# PortableECG.net
KiCad netlist of a schematic drawn in EAGLE
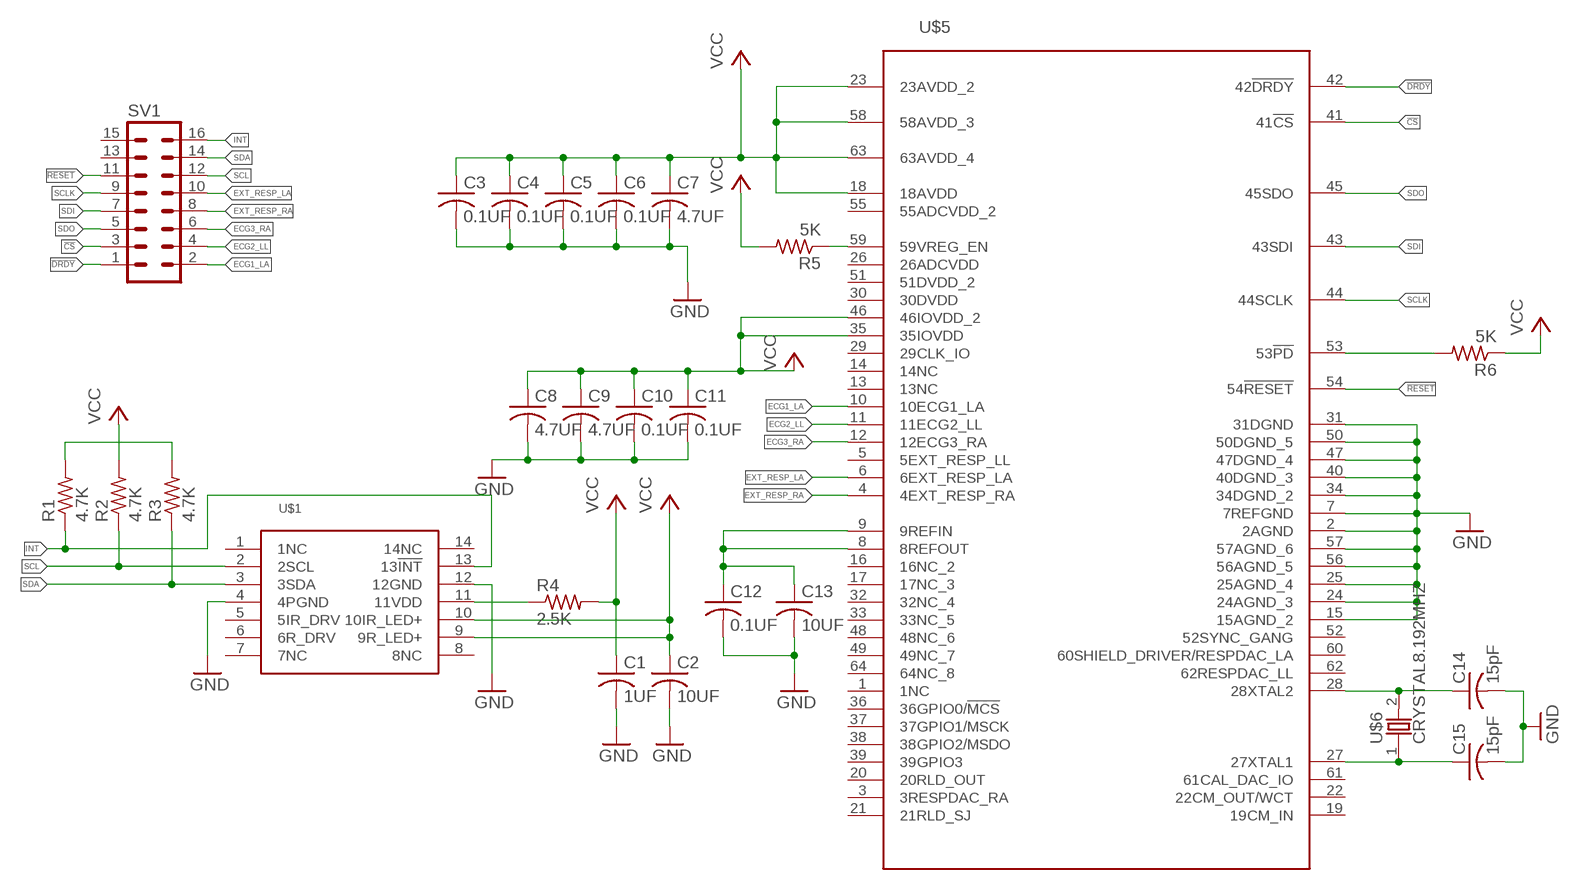
[diagram p0: schematic, sheet 1]

(export (version "E")
  (design (tool "Eeschema 10.0.6"))
  (components
    (comp (ref "C1")
      (value "1UF")
      (footprint "eagle-import:C075-063X106")
      (libsource (lib "eagle-import") (part "C-US075-063X106"))
    )
    (comp (ref "C2")
      (value "10UF")
      (footprint "eagle-import:C075-063X106")
      (libsource (lib "eagle-import") (part "C-US075-063X106"))
    )
    (comp (ref "C3")
      (value "0.1UF")
      (footprint "eagle-import:C075-063X106")
      (libsource (lib "eagle-import") (part "C-US075-063X106"))
    )
    (comp (ref "C4")
      (value "0.1UF")
      (footprint "eagle-import:C075-063X106")
      (libsource (lib "eagle-import") (part "C-US075-063X106"))
    )
    (comp (ref "C5")
      (value "0.1UF")
      (footprint "eagle-import:C075-063X106")
      (libsource (lib "eagle-import") (part "C-US075-063X106"))
    )
    (comp (ref "C6")
      (value "0.1UF")
      (footprint "eagle-import:C075-063X106")
      (libsource (lib "eagle-import") (part "C-US075-063X106"))
    )
    (comp (ref "C7")
      (value "4.7UF")
      (footprint "eagle-import:C075-063X106")
      (libsource (lib "eagle-import") (part "C-US075-063X106"))
    )
    (comp (ref "C8")
      (value "4.7UF")
      (footprint "eagle-import:C075-063X106")
      (libsource (lib "eagle-import") (part "C-US075-063X106"))
    )
    (comp (ref "C9")
      (value "4.7UF")
      (footprint "eagle-import:C075-063X106")
      (libsource (lib "eagle-import") (part "C-US075-063X106"))
    )
    (comp (ref "C10")
      (value "0.1UF")
      (footprint "eagle-import:C075-063X106")
      (libsource (lib "eagle-import") (part "C-US075-063X106"))
    )
    (comp (ref "C11")
      (value "0.1UF")
      (footprint "eagle-import:C075-063X106")
      (libsource (lib "eagle-import") (part "C-US075-063X106"))
    )
    (comp (ref "C12")
      (value "0.1UF")
      (footprint "eagle-import:C075-063X106")
      (libsource (lib "eagle-import") (part "C-US075-063X106"))
    )
    (comp (ref "C13")
      (value "10UF")
      (footprint "eagle-import:C075-063X106")
      (libsource (lib "eagle-import") (part "C-US075-063X106"))
    )
    (comp (ref "C14")
      (value "15pF")
      (footprint "eagle-import:C075-063X106")
      (libsource (lib "eagle-import") (part "C-US075-063X106"))
    )
    (comp (ref "C15")
      (value "15pF")
      (footprint "eagle-import:C075-063X106")
      (libsource (lib "eagle-import") (part "C-US075-063X106"))
    )
    (comp (ref "R1")
      (value "4.7K")
      (footprint "eagle-import:0207_12")
      (libsource (lib "eagle-import") (part "R-US_0207/12"))
    )
    (comp (ref "R2")
      (value "4.7K")
      (footprint "eagle-import:0207_12")
      (libsource (lib "eagle-import") (part "R-US_0207/12"))
    )
    (comp (ref "R3")
      (value "4.7K")
      (footprint "eagle-import:0207_12")
      (libsource (lib "eagle-import") (part "R-US_0207/12"))
    )
    (comp (ref "R4")
      (value "2.5K")
      (footprint "eagle-import:0207_12")
      (libsource (lib "eagle-import") (part "R-US_0207/12"))
    )
    (comp (ref "R5")
      (value "5K")
      (footprint "eagle-import:0207_12")
      (libsource (lib "eagle-import") (part "R-US_0207/12"))
    )
    (comp (ref "R6")
      (value "5K")
      (footprint "eagle-import:0207_12")
      (libsource (lib "eagle-import") (part "R-US_0207/12"))
    )
    (comp (ref "SV1")
      (value "16P")
      (footprint "eagle-import:16P")
      (libsource (lib "eagle-import") (part "16P"))
    )
    (comp (ref "U$1")
      (value "MAX30100DP")
      (footprint "eagle-import:MAX30100DP")
      (libsource (lib "eagle-import") (part "MAX30100DP"))
    )
    (comp (ref "U$5")
      (value "ADAS1000-4BSTZDP")
      (footprint "eagle-import:ADAS1000-4BSTZDP")
      (libsource (lib "eagle-import") (part "ADAS1000-4BSTZDP"))
    )
    (comp (ref "U$6")
      (value "CRYSTAL8.192MHZ")
      (footprint "eagle-import:CRYSTAL8.192MHZ")
      (libsource (lib "eagle-import") (part "CRYSTAL8.192MHZ"))
    )
  )
  (nets
    (net (code "1") (name "/~{CS}") (class "Default")
      (node (ref "SV1") (pin "3") (pinfunction "3_3") (pintype "passive"))
      (node (ref "U$5") (pin "41") (pinfunction "41~{CS}_41") (pintype "bidirectional"))
    )
    (net (code "2") (name "/~{DRDY}") (class "Default")
      (node (ref "SV1") (pin "1") (pinfunction "1_1") (pintype "passive"))
      (node (ref "U$5") (pin "42") (pinfunction "42~{DRDY}_42") (pintype "output"))
    )
    (net (code "3") (name "/~{RESET}") (class "Default")
      (node (ref "SV1") (pin "11") (pinfunction "11_11") (pintype "passive"))
      (node (ref "U$5") (pin "54") (pinfunction "54~{RESET}_54") (pintype "bidirectional"))
    )
    (net (code "4") (name "ECG1_LA") (class "Default")
      (node (ref "SV1") (pin "2") (pinfunction "2_2") (pintype "passive"))
      (node (ref "U$5") (pin "10") (pinfunction "10ECG1_LA_10") (pintype "bidirectional"))
    )
    (net (code "5") (name "ECG2_LL") (class "Default")
      (node (ref "SV1") (pin "4") (pinfunction "4_4") (pintype "passive"))
      (node (ref "U$5") (pin "11") (pinfunction "11ECG2_LL_11") (pintype "bidirectional"))
    )
    (net (code "6") (name "ECG3_RA") (class "Default")
      (node (ref "SV1") (pin "6") (pinfunction "6_6") (pintype "passive"))
      (node (ref "U$5") (pin "12") (pinfunction "12ECG3_RA_12") (pintype "bidirectional"))
    )
    (net (code "7") (name "EXT_RESP_LA") (class "Default")
      (node (ref "SV1") (pin "10") (pinfunction "10_10") (pintype "passive"))
      (node (ref "U$5") (pin "6") (pinfunction "6EXT_RESP_LA_6") (pintype "bidirectional"))
    )
    (net (code "8") (name "EXT_RESP_RA") (class "Default")
      (node (ref "SV1") (pin "8") (pinfunction "8_8") (pintype "passive"))
      (node (ref "U$5") (pin "4") (pinfunction "4EXT_RESP_RA_4") (pintype "bidirectional"))
    )
    (net (code "9") (name "GND") (class "Default")
      (node (ref "C1") (pin "2") (pinfunction "2_2") (pintype "passive"))
      (node (ref "C10") (pin "2") (pinfunction "2_2") (pintype "passive"))
      (node (ref "C11") (pin "2") (pinfunction "2_2") (pintype "passive"))
      (node (ref "C12") (pin "2") (pinfunction "2_2") (pintype "passive"))
      (node (ref "C13") (pin "2") (pinfunction "2_2") (pintype "passive"))
      (node (ref "C14") (pin "2") (pinfunction "2_2") (pintype "passive"))
      (node (ref "C15") (pin "2") (pinfunction "2_2") (pintype "passive"))
      (node (ref "C2") (pin "2") (pinfunction "2_2") (pintype "passive"))
      (node (ref "C3") (pin "2") (pinfunction "2_2") (pintype "passive"))
      (node (ref "C4") (pin "2") (pinfunction "2_2") (pintype "passive"))
      (node (ref "C5") (pin "2") (pinfunction "2_2") (pintype "passive"))
      (node (ref "C6") (pin "2") (pinfunction "2_2") (pintype "passive"))
      (node (ref "C7") (pin "2") (pinfunction "2_2") (pintype "passive"))
      (node (ref "C8") (pin "2") (pinfunction "2_2") (pintype "passive"))
      (node (ref "C9") (pin "2") (pinfunction "2_2") (pintype "passive"))
      (node (ref "U$1") (pin "12") (pinfunction "12GND_12") (pintype "bidirectional"))
      (node (ref "U$1") (pin "4") (pinfunction "4PGND_4") (pintype "bidirectional"))
      (node (ref "U$5") (pin "15") (pinfunction "15AGND_2_15") (pintype "bidirectional"))
      (node (ref "U$5") (pin "2") (pinfunction "2AGND_2") (pintype "bidirectional"))
      (node (ref "U$5") (pin "24") (pinfunction "24AGND_3_24") (pintype "bidirectional"))
      (node (ref "U$5") (pin "25") (pinfunction "25AGND_4_25") (pintype "bidirectional"))
      (node (ref "U$5") (pin "31") (pinfunction "31DGND_31") (pintype "bidirectional"))
      (node (ref "U$5") (pin "34") (pinfunction "34DGND_2_34") (pintype "bidirectional"))
      (node (ref "U$5") (pin "40") (pinfunction "40DGND_3_40") (pintype "bidirectional"))
      (node (ref "U$5") (pin "47") (pinfunction "47DGND_4_47") (pintype "bidirectional"))
      (node (ref "U$5") (pin "50") (pinfunction "50DGND_5_50") (pintype "bidirectional"))
      (node (ref "U$5") (pin "56") (pinfunction "56AGND_5_56") (pintype "bidirectional"))
      (node (ref "U$5") (pin "57") (pinfunction "57AGND_6_57") (pintype "bidirectional"))
      (node (ref "U$5") (pin "7") (pinfunction "7REFGND_7") (pintype "bidirectional"))
    )
    (net (code "10") (name "INT") (class "Default")
      (node (ref "R1") (pin "1") (pinfunction "1_1") (pintype "passive"))
      (node (ref "SV1") (pin "16") (pinfunction "16_16") (pintype "passive"))
      (node (ref "U$1") (pin "13") (pinfunction "13~{INT}_13") (pintype "bidirectional"))
    )
    (net (code "11") (name "Net-(R1-Pad2)") (class "Default")
      (node (ref "R1") (pin "2") (pinfunction "2_2") (pintype "passive"))
      (node (ref "R3") (pin "2") (pinfunction "2_2") (pintype "passive"))
    )
    (net (code "12") (name "Net-(U$1-11VDD)") (class "Default")
      (node (ref "R4") (pin "1") (pinfunction "1_1") (pintype "passive"))
      (node (ref "U$1") (pin "11") (pinfunction "11VDD_11") (pintype "bidirectional"))
    )
    (net (code "13") (name "Net-(U$5-8REFOUT)") (class "Default")
      (node (ref "C12") (pin "1") (pinfunction "1_1") (pintype "passive"))
      (node (ref "C13") (pin "1") (pinfunction "1_1") (pintype "passive"))
      (node (ref "U$5") (pin "8") (pinfunction "8REFOUT_8") (pintype "output"))
      (node (ref "U$5") (pin "9") (pinfunction "9REFIN_9") (pintype "input"))
    )
    (net (code "14") (name "Net-(U$5-27XTAL1)") (class "Default")
      (node (ref "C15") (pin "1") (pinfunction "1_1") (pintype "passive"))
      (node (ref "U$5") (pin "27") (pinfunction "27XTAL1_27") (pintype "bidirectional"))
      (node (ref "U$6") (pin "1") (pinfunction "1_1") (pintype "passive"))
    )
    (net (code "15") (name "Net-(U$5-28XTAL2)") (class "Default")
      (node (ref "C14") (pin "1") (pinfunction "1_1") (pintype "passive"))
      (node (ref "U$5") (pin "28") (pinfunction "28XTAL2_28") (pintype "bidirectional"))
      (node (ref "U$6") (pin "2") (pinfunction "2_2") (pintype "passive"))
    )
    (net (code "16") (name "Net-(U$5-53~{PD})") (class "Default")
      (node (ref "R6") (pin "2") (pinfunction "2_2") (pintype "passive"))
      (node (ref "U$5") (pin "53") (pinfunction "53~{PD}_53") (pintype "bidirectional"))
    )
    (net (code "17") (name "Net-(U$5-59VREG_EN)") (class "Default")
      (node (ref "R5") (pin "1") (pinfunction "1_1") (pintype "passive"))
      (node (ref "U$5") (pin "59") (pinfunction "59VREG_EN_59") (pintype "bidirectional"))
    )
    (net (code "18") (name "SCL") (class "Default")
      (node (ref "R2") (pin "1") (pinfunction "1_1") (pintype "passive"))
      (node (ref "SV1") (pin "12") (pinfunction "12_12") (pintype "passive"))
      (node (ref "U$1") (pin "2") (pinfunction "2SCL_2") (pintype "input"))
    )
    (net (code "19") (name "SCLK") (class "Default")
      (node (ref "SV1") (pin "9") (pinfunction "9_9") (pintype "passive"))
      (node (ref "U$5") (pin "44") (pinfunction "44SCLK_44") (pintype "bidirectional"))
    )
    (net (code "20") (name "SDA") (class "Default")
      (node (ref "R3") (pin "1") (pinfunction "1_1") (pintype "passive"))
      (node (ref "SV1") (pin "14") (pinfunction "14_14") (pintype "passive"))
      (node (ref "U$1") (pin "3") (pinfunction "3SDA_3") (pintype "bidirectional"))
    )
    (net (code "21") (name "SDI") (class "Default")
      (node (ref "SV1") (pin "7") (pinfunction "7_7") (pintype "passive"))
      (node (ref "U$5") (pin "43") (pinfunction "43SDI_43") (pintype "input"))
    )
    (net (code "22") (name "SDO") (class "Default")
      (node (ref "SV1") (pin "5") (pinfunction "5_5") (pintype "passive"))
      (node (ref "U$5") (pin "45") (pinfunction "45SDO_45") (pintype "output"))
    )
    (net (code "23") (name "VCC") (class "Default")
      (node (ref "C1") (pin "1") (pinfunction "1_1") (pintype "passive"))
      (node (ref "C10") (pin "1") (pinfunction "1_1") (pintype "passive"))
      (node (ref "C11") (pin "1") (pinfunction "1_1") (pintype "passive"))
      (node (ref "C2") (pin "1") (pinfunction "1_1") (pintype "passive"))
      (node (ref "C3") (pin "1") (pinfunction "1_1") (pintype "passive"))
      (node (ref "C4") (pin "1") (pinfunction "1_1") (pintype "passive"))
      (node (ref "C5") (pin "1") (pinfunction "1_1") (pintype "passive"))
      (node (ref "C6") (pin "1") (pinfunction "1_1") (pintype "passive"))
      (node (ref "C7") (pin "1") (pinfunction "1_1") (pintype "passive"))
      (node (ref "C8") (pin "1") (pinfunction "1_1") (pintype "passive"))
      (node (ref "C9") (pin "1") (pinfunction "1_1") (pintype "passive"))
      (node (ref "R2") (pin "2") (pinfunction "2_2") (pintype "passive"))
      (node (ref "R4") (pin "2") (pinfunction "2_2") (pintype "passive"))
      (node (ref "R5") (pin "2") (pinfunction "2_2") (pintype "passive"))
      (node (ref "R6") (pin "1") (pinfunction "1_1") (pintype "passive"))
      (node (ref "U$1") (pin "10") (pinfunction "10IR_LED+_10") (pintype "bidirectional"))
      (node (ref "U$1") (pin "9") (pinfunction "9R_LED+_9") (pintype "bidirectional"))
      (node (ref "U$5") (pin "18") (pinfunction "18AVDD_18") (pintype "bidirectional"))
      (node (ref "U$5") (pin "23") (pinfunction "23AVDD_2_23") (pintype "bidirectional"))
      (node (ref "U$5") (pin "35") (pinfunction "35IOVDD_35") (pintype "bidirectional"))
      (node (ref "U$5") (pin "46") (pinfunction "46IOVDD_2_46") (pintype "bidirectional"))
      (node (ref "U$5") (pin "58") (pinfunction "58AVDD_3_58") (pintype "bidirectional"))
      (node (ref "U$5") (pin "63") (pinfunction "63AVDD_4_63") (pintype "bidirectional"))
    )
    (net (code "24") (name "unconnected-(SV1-Pad13)") (class "Default")
      (node (ref "SV1") (pin "13") (pinfunction "13_13") (pintype "passive"))
    )
    (net (code "25") (name "unconnected-(SV1-Pad15)") (class "Default")
      (node (ref "SV1") (pin "15") (pinfunction "15_15") (pintype "passive"))
    )
    (net (code "26") (name "unconnected-(U$1-1NC-Pad1)") (class "Default")
      (node (ref "U$1") (pin "1") (pinfunction "1NC_1") (pintype "no_connect"))
    )
    (net (code "27") (name "unconnected-(U$1-5IR_DRV-Pad5)") (class "Default")
      (node (ref "U$1") (pin "5") (pinfunction "5IR_DRV_5") (pintype "no_connect"))
    )
    (net (code "28") (name "unconnected-(U$1-6R_DRV-Pad6)") (class "Default")
      (node (ref "U$1") (pin "6") (pinfunction "6R_DRV_6") (pintype "no_connect"))
    )
    (net (code "29") (name "unconnected-(U$1-7NC-Pad7)") (class "Default")
      (node (ref "U$1") (pin "7") (pinfunction "7NC_7") (pintype "no_connect"))
    )
    (net (code "30") (name "unconnected-(U$1-8NC-Pad8)") (class "Default")
      (node (ref "U$1") (pin "8") (pinfunction "8NC_8") (pintype "no_connect"))
    )
    (net (code "31") (name "unconnected-(U$1-14NC-Pad14)") (class "Default")
      (node (ref "U$1") (pin "14") (pinfunction "14NC_14") (pintype "no_connect"))
    )
    (net (code "32") (name "unconnected-(U$5-1NC-Pad1)") (class "Default")
      (node (ref "U$5") (pin "1") (pinfunction "1NC_1") (pintype "no_connect"))
    )
    (net (code "33") (name "unconnected-(U$5-3RESPDAC_RA-Pad3)") (class "Default")
      (node (ref "U$5") (pin "3") (pinfunction "3RESPDAC_RA_3") (pintype "no_connect"))
    )
    (net (code "34") (name "unconnected-(U$5-5EXT_RESP_LL-Pad5)") (class "Default")
      (node (ref "U$5") (pin "5") (pinfunction "5EXT_RESP_LL_5") (pintype "no_connect"))
    )
    (net (code "35") (name "unconnected-(U$5-13NC-Pad13)") (class "Default")
      (node (ref "U$5") (pin "13") (pinfunction "13NC_13") (pintype "no_connect"))
    )
    (net (code "36") (name "unconnected-(U$5-14NC-Pad14)") (class "Default")
      (node (ref "U$5") (pin "14") (pinfunction "14NC_14") (pintype "no_connect"))
    )
    (net (code "37") (name "unconnected-(U$5-16NC_2-Pad16)") (class "Default")
      (node (ref "U$5") (pin "16") (pinfunction "16NC_2_16") (pintype "bidirectional"))
    )
    (net (code "38") (name "unconnected-(U$5-17NC_3-Pad17)") (class "Default")
      (node (ref "U$5") (pin "17") (pinfunction "17NC_3_17") (pintype "bidirectional"))
    )
    (net (code "39") (name "unconnected-(U$5-19CM_IN-Pad19)") (class "Default")
      (node (ref "U$5") (pin "19") (pinfunction "19CM_IN_19") (pintype "no_connect"))
    )
    (net (code "40") (name "unconnected-(U$5-20RLD_OUT-Pad20)") (class "Default")
      (node (ref "U$5") (pin "20") (pinfunction "20RLD_OUT_20") (pintype "no_connect"))
    )
    (net (code "41") (name "unconnected-(U$5-21RLD_SJ-Pad21)") (class "Default")
      (node (ref "U$5") (pin "21") (pinfunction "21RLD_SJ_21") (pintype "no_connect"))
    )
    (net (code "42") (name "unconnected-(U$5-22CM_OUT{slash}WCT-Pad22)") (class "Default")
      (node (ref "U$5") (pin "22") (pinfunction "22CM_OUT/WCT_22") (pintype "no_connect"))
    )
    (net (code "43") (name "unconnected-(U$5-26ADCVDD-Pad26)") (class "Default")
      (node (ref "U$5") (pin "26") (pinfunction "26ADCVDD_26") (pintype "no_connect"))
    )
    (net (code "44") (name "unconnected-(U$5-29CLK_IO-Pad29)") (class "Default")
      (node (ref "U$5") (pin "29") (pinfunction "29CLK_IO_29") (pintype "no_connect"))
    )
    (net (code "45") (name "unconnected-(U$5-30DVDD-Pad30)") (class "Default")
      (node (ref "U$5") (pin "30") (pinfunction "30DVDD_30") (pintype "no_connect"))
    )
    (net (code "46") (name "unconnected-(U$5-32NC_4-Pad32)") (class "Default")
      (node (ref "U$5") (pin "32") (pinfunction "32NC_4_32") (pintype "no_connect"))
    )
    (net (code "47") (name "unconnected-(U$5-33NC_5-Pad33)") (class "Default")
      (node (ref "U$5") (pin "33") (pinfunction "33NC_5_33") (pintype "no_connect"))
    )
    (net (code "48") (name "unconnected-(U$5-36GPIO0{slash}~{MCS}-Pad36)") (class "Default")
      (node (ref "U$5") (pin "36") (pinfunction "36GPIO0/~{MCS}_36") (pintype "no_connect"))
    )
    (net (code "49") (name "unconnected-(U$5-37GPIO1{slash}MSCK-Pad37)") (class "Default")
      (node (ref "U$5") (pin "37") (pinfunction "37GPIO1/MSCK_37") (pintype "no_connect"))
    )
    (net (code "50") (name "unconnected-(U$5-38GPIO2{slash}MSDO-Pad38)") (class "Default")
      (node (ref "U$5") (pin "38") (pinfunction "38GPIO2/MSDO_38") (pintype "no_connect"))
    )
    (net (code "51") (name "unconnected-(U$5-39GPIO3-Pad39)") (class "Default")
      (node (ref "U$5") (pin "39") (pinfunction "39GPIO3_39") (pintype "no_connect"))
    )
    (net (code "52") (name "unconnected-(U$5-48NC_6-Pad48)") (class "Default")
      (node (ref "U$5") (pin "48") (pinfunction "48NC_6_48") (pintype "no_connect"))
    )
    (net (code "53") (name "unconnected-(U$5-49NC_7-Pad49)") (class "Default")
      (node (ref "U$5") (pin "49") (pinfunction "49NC_7_49") (pintype "no_connect"))
    )
    (net (code "54") (name "unconnected-(U$5-51DVDD_2-Pad51)") (class "Default")
      (node (ref "U$5") (pin "51") (pinfunction "51DVDD_2_51") (pintype "no_connect"))
    )
    (net (code "55") (name "unconnected-(U$5-52SYNC_GANG-Pad52)") (class "Default")
      (node (ref "U$5") (pin "52") (pinfunction "52SYNC_GANG_52") (pintype "no_connect"))
    )
    (net (code "56") (name "unconnected-(U$5-55ADCVDD_2-Pad55)") (class "Default")
      (node (ref "U$5") (pin "55") (pinfunction "55ADCVDD_2_55") (pintype "no_connect"))
    )
    (net (code "57") (name "unconnected-(U$5-60SHIELD_DRIVER{slash}RESPDAC_LA-Pad60)") (class "Default")
      (node (ref "U$5") (pin "60") (pinfunction "60SHIELD_DRIVER/RESPDAC_LA_60") (pintype "no_connect"))
    )
    (net (code "58") (name "unconnected-(U$5-61CAL_DAC_IO-Pad61)") (class "Default")
      (node (ref "U$5") (pin "61") (pinfunction "61CAL_DAC_IO_61") (pintype "bidirectional"))
    )
    (net (code "59") (name "unconnected-(U$5-62RESPDAC_LL-Pad62)") (class "Default")
      (node (ref "U$5") (pin "62") (pinfunction "62RESPDAC_LL_62") (pintype "no_connect"))
    )
    (net (code "60") (name "unconnected-(U$5-64NC_8-Pad64)") (class "Default")
      (node (ref "U$5") (pin "64") (pinfunction "64NC_8_64") (pintype "no_connect"))
    )
  )
)
